# Soccer_Robot_V1_1L.net
KiCad netlist of a schematic drawn in EAGLE
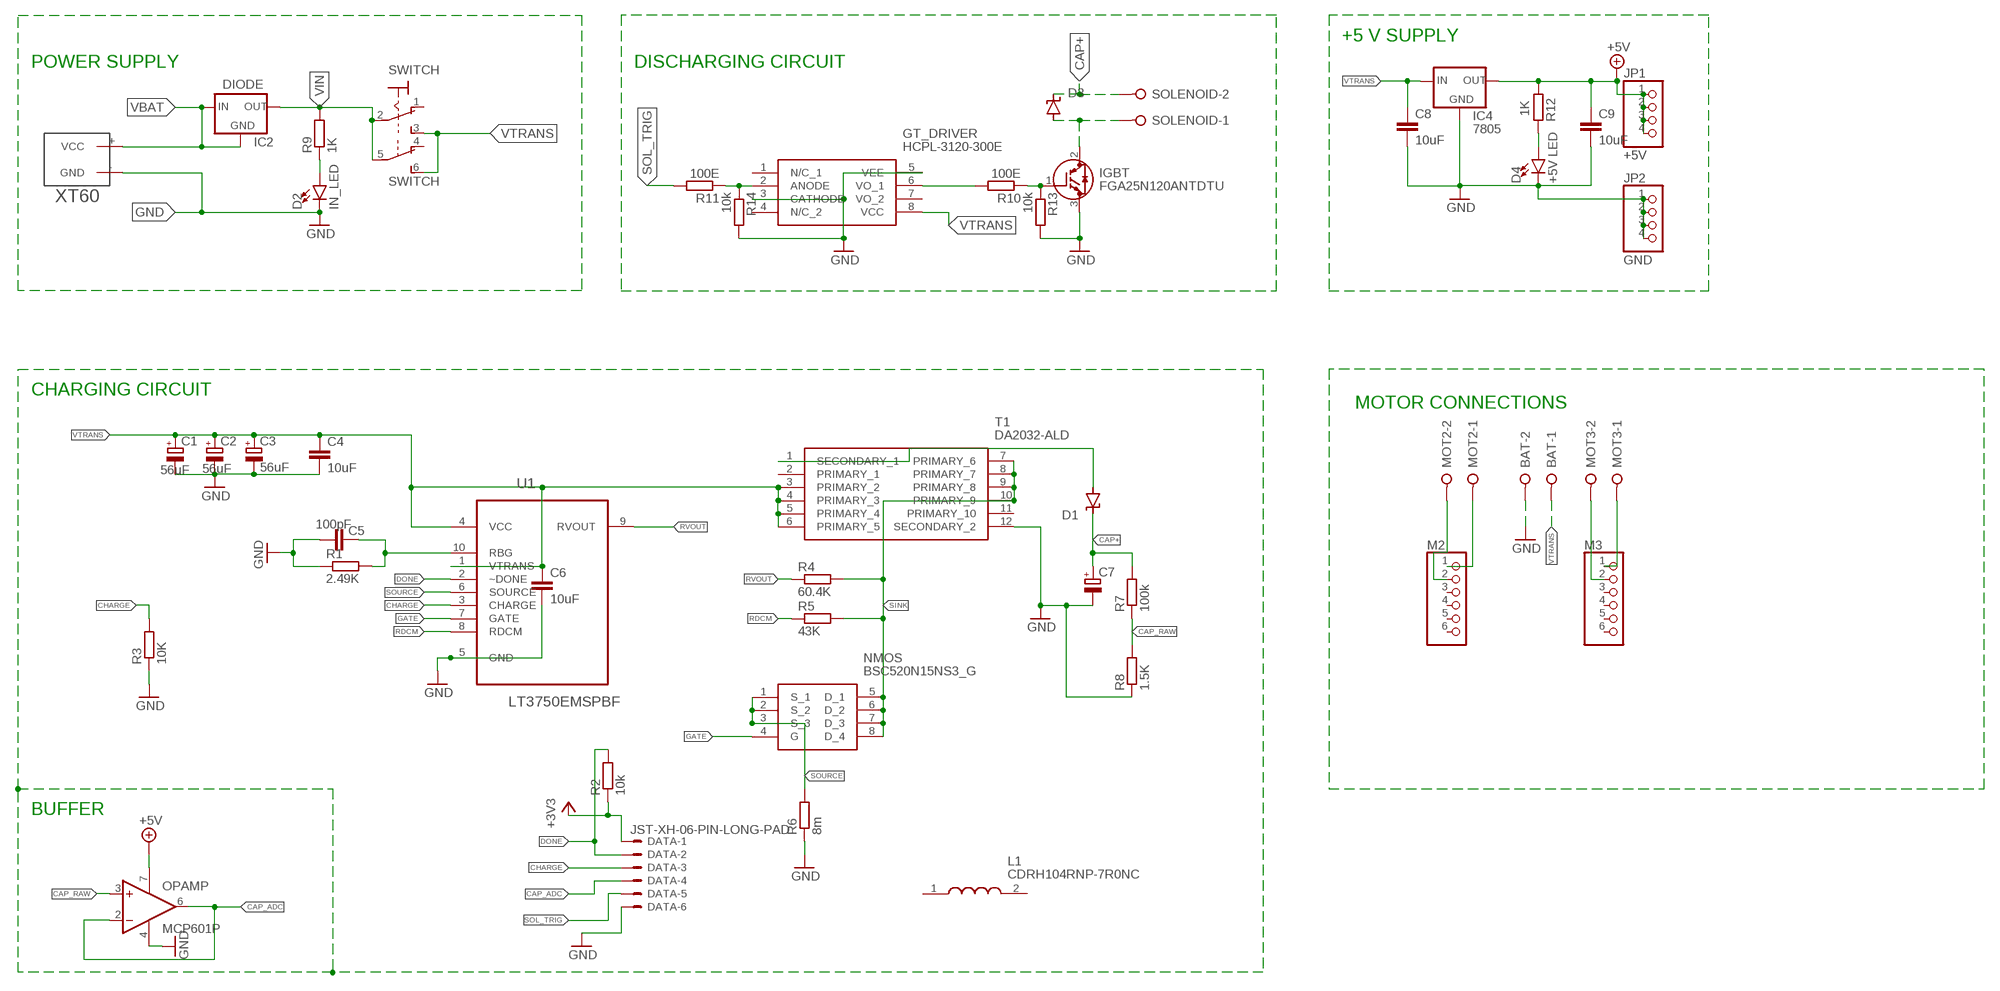
[diagram p0: schematic, sheet 1]

(export (version "E")
  (design (tool "Eeschema 10.0.6"))
  (components
    (comp (ref "BAT")
      (value "W237-02P")
      (footprint "eagle-import:W237-132")
      (libsource (lib "eagle-import") (part "W237-02P"))
    )
    (comp (ref "C1")
      (value "56uF")
      (footprint "eagle-import:E2,5-5")
      (libsource (lib "eagle-import") (part "CPOL-EUE2.5-5"))
    )
    (comp (ref "C2")
      (value "56uF")
      (footprint "eagle-import:E2,5-5")
      (libsource (lib "eagle-import") (part "CPOL-EUE2.5-5"))
    )
    (comp (ref "C3")
      (value "56uF")
      (footprint "eagle-import:E2,5-5")
      (libsource (lib "eagle-import") (part "CPOL-EUE2.5-5"))
    )
    (comp (ref "C4")
      (value "10uF")
      (footprint "eagle-import:C1206")
      (libsource (lib "eagle-import") (part "C-EUC1206"))
    )
    (comp (ref "C5")
      (value "100pF")
      (footprint "eagle-import:C1206")
      (libsource (lib "eagle-import") (part "C-EUC1206"))
    )
    (comp (ref "C6")
      (value "10uF")
      (footprint "eagle-import:C1206")
      (libsource (lib "eagle-import") (part "C-EUC1206"))
    )
    (comp (ref "C7")
      (value "CPOL-EUE10-30")
      (footprint "eagle-import:EB30D")
      (libsource (lib "eagle-import") (part "CPOL-EUE10-30"))
    )
    (comp (ref "C8")
      (value "10uF")
      (footprint "eagle-import:C1206")
      (libsource (lib "eagle-import") (part "C-EUC1206"))
    )
    (comp (ref "C9")
      (value "10uF")
      (footprint "eagle-import:C1206")
      (libsource (lib "eagle-import") (part "C-EUC1206"))
    )
    (comp (ref "D1")
      (value "SUPPRESSOR-SMBG")
      (footprint "eagle-import:SMBG")
      (libsource (lib "eagle-import") (part "SUPPRESSOR-SMBG"))
    )
    (comp (ref "D2")
      (value "IN_LED")
      (footprint "eagle-import:LED_5MM")
      (libsource (lib "eagle-import") (part "LED5MM"))
    )
    (comp (ref "D3")
      (value "SUPPRESSOR-SMBG")
      (footprint "eagle-import:SMBG")
      (libsource (lib "eagle-import") (part "SUPPRESSOR-SMBG"))
    )
    (comp (ref "D4")
      (value "+5V LED")
      (footprint "eagle-import:LED_5MM")
      (libsource (lib "eagle-import") (part "LED5MM"))
    )
    (comp (ref "DATA")
      (value "JST-XH-06-PIN-LONG-PAD")
      (footprint "eagle-import:JST-XH-06-PACKAGE-LONG-PAD")
      (libsource (lib "eagle-import") (part "JST-XH-06-PIN-LONG-PAD"))
    )
    (comp (ref "GT_DRIVER")
      (value "HCPL-3120-300E")
      (footprint "eagle-import:HCPL-3120-GULL-WING")
      (fields (field (name "MOUSER_PART_NUMBER") "630-HCPL-3120-300E"))
      (libsource (lib "eagle-import") (part "HCPL-3120-300E"))
    )
    (comp (ref "IC2")
      (value "DIODE")
      (footprint "eagle-import:TO252")
      (libsource (lib "eagle-import") (part "LM1117TO252"))
    )
    (comp (ref "IC4")
      (value "7805")
      (footprint "eagle-import:78XXS")
      (libsource (lib "eagle-import") (part "78XXS"))
    )
    (comp (ref "IGBT")
      (value "FGA25N120ANTDTU")
      (footprint "eagle-import:TO545P500X1560X2420-3P")
      (fields (field (name "MOUSER_PART_NUMBER") "512-FGA25N120ANTDTU"))
      (libsource (lib "eagle-import") (part "FGA25N120ANTDTU"))
    )
    (comp (ref "JP1")
      (value "+5V")
      (footprint "eagle-import:1X04")
      (libsource (lib "eagle-import") (part "PINHD-1X4"))
    )
    (comp (ref "JP2")
      (value "GND")
      (footprint "eagle-import:1X04")
      (libsource (lib "eagle-import") (part "PINHD-1X4"))
    )
    (comp (ref "L1")
      (value "CDRH104RNP-7R0NC")
      (footprint "eagle-import:CDRH104RNP7R0NC")
      (fields (field (name "MOUSER_PART_NUMBER") "851-CDRH104RNP-7R0NC"))
      (libsource (lib "eagle-import") (part "CDRH104RNP-7R0NC"))
    )
    (comp (ref "M2")
      (value "PINHD-1X6")
      (footprint "eagle-import:1X06")
      (libsource (lib "eagle-import") (part "PINHD-1X6"))
    )
    (comp (ref "M3")
      (value "PINHD-1X6")
      (footprint "eagle-import:1X06")
      (libsource (lib "eagle-import") (part "PINHD-1X6"))
    )
    (comp (ref "MOT2")
      (value "W237-02P")
      (footprint "eagle-import:W237-132")
      (libsource (lib "eagle-import") (part "W237-02P"))
    )
    (comp (ref "MOT3")
      (value "W237-02P")
      (footprint "eagle-import:W237-132")
      (libsource (lib "eagle-import") (part "W237-02P"))
    )
    (comp (ref "NMOS")
      (value "BSC520N15NS3_G")
      (footprint "eagle-import:PG-TDSON-8")
      (fields
        (field (name "MANUFACTURER_PART_NUMBER") "BSC520N15NS3 G")
        (field (name "MOUSER_PART_NUMBER") "726-BSC520N15NS3GXT")
      )
      (libsource (lib "eagle-import") (part "BSC520N15NS3_G"))
    )
    (comp (ref "OPAMP")
      (value "MCP601P")
      (footprint "eagle-import:DIL08")
      (libsource (lib "eagle-import") (part "MCP601P"))
    )
    (comp (ref "R1")
      (value "2.49K")
      (footprint "eagle-import:M1206")
      (libsource (lib "eagle-import") (part "R-EU_M1206"))
    )
    (comp (ref "R2")
      (value "10k")
      (footprint "eagle-import:M1206")
      (libsource (lib "eagle-import") (part "R-EU_M1206"))
    )
    (comp (ref "R3")
      (value "10K")
      (footprint "eagle-import:M1206")
      (libsource (lib "eagle-import") (part "R-EU_M1206"))
    )
    (comp (ref "R4")
      (value "60.4K")
      (footprint "eagle-import:M1206")
      (libsource (lib "eagle-import") (part "R-EU_M1206"))
    )
    (comp (ref "R5")
      (value "43K")
      (footprint "eagle-import:M1206")
      (libsource (lib "eagle-import") (part "R-EU_M1206"))
    )
    (comp (ref "R6")
      (value "8m")
      (footprint "eagle-import:M1206")
      (libsource (lib "eagle-import") (part "R-EU_M1206"))
    )
    (comp (ref "R7")
      (value "100k")
      (footprint "eagle-import:0207_10")
      (libsource (lib "eagle-import") (part "R-EU_0207/10"))
    )
    (comp (ref "R8")
      (value "1.5K")
      (footprint "eagle-import:0207_10")
      (libsource (lib "eagle-import") (part "R-EU_0207/10"))
    )
    (comp (ref "R9")
      (value "1K")
      (footprint "eagle-import:M1206")
      (libsource (lib "eagle-import") (part "R-EU_M1206"))
    )
    (comp (ref "R10")
      (value "100E")
      (footprint "eagle-import:M1206")
      (libsource (lib "eagle-import") (part "R-EU_M1206"))
    )
    (comp (ref "R11")
      (value "100E")
      (footprint "eagle-import:M1206")
      (libsource (lib "eagle-import") (part "R-EU_M1206"))
    )
    (comp (ref "R12")
      (value "1K")
      (footprint "eagle-import:M1206")
      (libsource (lib "eagle-import") (part "R-EU_M1206"))
    )
    (comp (ref "R13")
      (value "10k")
      (footprint "eagle-import:M1206")
      (libsource (lib "eagle-import") (part "R-EU_M1206"))
    )
    (comp (ref "R14")
      (value "10k")
      (footprint "eagle-import:M1206")
      (libsource (lib "eagle-import") (part "R-EU_M1206"))
    )
    (comp (ref "SOLENOID")
      (value "W237-02P")
      (footprint "eagle-import:W237-132")
      (libsource (lib "eagle-import") (part "W237-02P"))
    )
    (comp (ref "SWITCH")
      (value "320-938")
      (footprint "eagle-import:320-938")
      (libsource (lib "eagle-import") (part "320-938"))
    )
    (comp (ref "T1")
      (value "DA2032-ALD")
      (footprint "eagle-import:SOP250P2197X889-12N")
      (fields (field (name "MOUSER_PART_NUMBER") "994-DA2032-ALD"))
      (libsource (lib "eagle-import") (part "DA2032-ALD"))
    )
    (comp (ref "U$1")
      (value "XT60")
      (footprint "eagle-import:XT60")
      (libsource (lib "eagle-import") (part "XT60"))
    )
    (comp (ref "U1")
      (value "LT3750EMSPBF")
      (footprint "eagle-import:SOP50P490X110-10N")
      (fields (field (name "MPN") "LT3750EMS#PBF"))
      (libsource (lib "eagle-import") (part "LT3750EMSPBF"))
    )
  )
  (nets
    (net (code "1") (name "+3V3") (class "Default")
      (node (ref "DATA") (pin "1") (pinfunction "S_1") (pintype "passive"))
      (node (ref "R2") (pin "1") (pinfunction "1_1") (pintype "passive"))
    )
    (net (code "2") (name "+5V") (class "Default")
      (node (ref "C9") (pin "1") (pinfunction "1_1") (pintype "passive"))
      (node (ref "IC4") (pin "OUT") (pinfunction "OUT_OUT") (pintype "passive"))
      (node (ref "JP1") (pin "1") (pinfunction "1_1") (pintype "passive"))
      (node (ref "JP1") (pin "2") (pinfunction "2_2") (pintype "passive"))
      (node (ref "JP1") (pin "3") (pinfunction "3_3") (pintype "passive"))
      (node (ref "JP1") (pin "4") (pinfunction "4_4") (pintype "passive"))
      (node (ref "OPAMP") (pin "7") (pinfunction "V+_7") (pintype "power_in"))
      (node (ref "R12") (pin "1") (pinfunction "1_1") (pintype "passive"))
    )
    (net (code "3") (name "CAP+") (class "Default")
      (node (ref "C7") (pin "+") (pinfunction "+_+") (pintype "passive"))
      (node (ref "D1") (pin "C") (pinfunction "C_C") (pintype "passive"))
      (node (ref "D3") (pin "C") (pinfunction "C_C") (pintype "passive"))
      (node (ref "R7") (pin "2") (pinfunction "2_2") (pintype "passive"))
      (node (ref "SOLENOID") (pin "2") (pinfunction "KL_2") (pintype "passive"))
    )
    (net (code "4") (name "CAP_ADC") (class "Default")
      (node (ref "DATA") (pin "4") (pinfunction "S_4") (pintype "passive"))
      (node (ref "OPAMP") (pin "2") (pinfunction "-IN_2") (pintype "input"))
      (node (ref "OPAMP") (pin "6") (pinfunction "OUT_6") (pintype "output"))
    )
    (net (code "5") (name "CAP_RAW") (class "Default")
      (node (ref "OPAMP") (pin "3") (pinfunction "+IN_3") (pintype "input"))
      (node (ref "R7") (pin "1") (pinfunction "1_1") (pintype "passive"))
      (node (ref "R8") (pin "2") (pinfunction "2_2") (pintype "passive"))
    )
    (net (code "6") (name "CHARGE") (class "Default")
      (node (ref "DATA") (pin "3") (pinfunction "S_3") (pintype "passive"))
      (node (ref "R3") (pin "2") (pinfunction "2_2") (pintype "passive"))
      (node (ref "U1") (pin "3") (pinfunction "CHARGE_3") (pintype "input"))
    )
    (net (code "7") (name "DONE") (class "Default")
      (node (ref "DATA") (pin "2") (pinfunction "S_2") (pintype "passive"))
      (node (ref "R2") (pin "2") (pinfunction "2_2") (pintype "passive"))
      (node (ref "U1") (pin "2") (pinfunction "~{DONE}_2") (pintype "input"))
    )
    (net (code "8") (name "GATE") (class "Default")
      (node (ref "NMOS") (pin "4") (pinfunction "G_4") (pintype "bidirectional"))
      (node (ref "U1") (pin "7") (pinfunction "GATE_7") (pintype "input"))
    )
    (net (code "9") (name "GND") (class "Default")
      (node (ref "BAT") (pin "2") (pinfunction "KL_2") (pintype "passive"))
      (node (ref "C1") (pin "-") (pinfunction "-_-") (pintype "passive"))
      (node (ref "C2") (pin "-") (pinfunction "-_-") (pintype "passive"))
      (node (ref "C3") (pin "-") (pinfunction "-_-") (pintype "passive"))
      (node (ref "C4") (pin "2") (pinfunction "2_2") (pintype "passive"))
      (node (ref "C5") (pin "2") (pinfunction "2_2") (pintype "passive"))
      (node (ref "C6") (pin "2") (pinfunction "2_2") (pintype "passive"))
      (node (ref "C7") (pin "-") (pinfunction "-_-") (pintype "passive"))
      (node (ref "C8") (pin "2") (pinfunction "2_2") (pintype "passive"))
      (node (ref "C9") (pin "2") (pinfunction "2_2") (pintype "passive"))
      (node (ref "D2") (pin "K") (pinfunction "C_K") (pintype "passive"))
      (node (ref "D4") (pin "K") (pinfunction "C_K") (pintype "passive"))
      (node (ref "DATA") (pin "6") (pinfunction "S_6") (pintype "passive"))
      (node (ref "GT_DRIVER") (pin "3") (pinfunction "CATHODE_3") (pintype "bidirectional"))
      (node (ref "GT_DRIVER") (pin "5") (pinfunction "VEE_5") (pintype "bidirectional"))
      (node (ref "IC4") (pin "GND") (pinfunction "GND_GND") (pintype "input"))
      (node (ref "IGBT") (pin "3") (pinfunction "E_3") (pintype "bidirectional"))
      (node (ref "JP2") (pin "1") (pinfunction "1_1") (pintype "passive"))
      (node (ref "JP2") (pin "2") (pinfunction "2_2") (pintype "passive"))
      (node (ref "JP2") (pin "3") (pinfunction "3_3") (pintype "passive"))
      (node (ref "JP2") (pin "4") (pinfunction "4_4") (pintype "passive"))
      (node (ref "OPAMP") (pin "4") (pinfunction "V-_4") (pintype "power_in"))
      (node (ref "R1") (pin "1") (pinfunction "1_1") (pintype "passive"))
      (node (ref "R13") (pin "2") (pinfunction "2_2") (pintype "passive"))
      (node (ref "R14") (pin "2") (pinfunction "2_2") (pintype "passive"))
      (node (ref "R3") (pin "1") (pinfunction "1_1") (pintype "passive"))
      (node (ref "R6") (pin "1") (pinfunction "1_1") (pintype "passive"))
      (node (ref "R8") (pin "1") (pinfunction "1_1") (pintype "passive"))
      (node (ref "T1") (pin "12") (pinfunction "SECONDARY_2_12") (pintype "bidirectional"))
      (node (ref "U$1") (pin "-") (pinfunction "GND_-") (pintype "bidirectional"))
      (node (ref "U1") (pin "5") (pinfunction "GND_5") (pintype "passive"))
    )
    (net (code "10") (name "Net-(D2-PadA)") (class "Default")
      (node (ref "D2") (pin "A") (pinfunction "A_A") (pintype "passive"))
      (node (ref "R9") (pin "1") (pinfunction "1_1") (pintype "passive"))
    )
    (net (code "11") (name "Net-(D4-PadA)") (class "Default")
      (node (ref "D4") (pin "A") (pinfunction "A_A") (pintype "passive"))
      (node (ref "R12") (pin "2") (pinfunction "2_2") (pintype "passive"))
    )
    (net (code "12") (name "Net-(GT_DRIVER-ANODE)") (class "Default")
      (node (ref "GT_DRIVER") (pin "2") (pinfunction "ANODE_2") (pintype "bidirectional"))
      (node (ref "R11") (pin "1") (pinfunction "1_1") (pintype "passive"))
      (node (ref "R14") (pin "1") (pinfunction "1_1") (pintype "passive"))
    )
    (net (code "13") (name "Net-(GT_DRIVER-VO_1)") (class "Default")
      (node (ref "GT_DRIVER") (pin "6") (pinfunction "VO_1_6") (pintype "bidirectional"))
      (node (ref "R10") (pin "2") (pinfunction "2_2") (pintype "passive"))
    )
    (net (code "14") (name "Net-(IGBT-C)") (class "Default")
      (node (ref "D3") (pin "A") (pinfunction "A_A") (pintype "passive"))
      (node (ref "IGBT") (pin "2") (pinfunction "C_2") (pintype "bidirectional"))
      (node (ref "SOLENOID") (pin "1") (pinfunction "KL_1") (pintype "passive"))
    )
    (net (code "15") (name "Net-(IGBT-G)") (class "Default")
      (node (ref "IGBT") (pin "1") (pinfunction "G_1") (pintype "bidirectional"))
      (node (ref "R10") (pin "1") (pinfunction "1_1") (pintype "passive"))
      (node (ref "R13") (pin "1") (pinfunction "1_1") (pintype "passive"))
    )
    (net (code "16") (name "Net-(MOT2A-KL)") (class "Default")
      (node (ref "M2") (pin "1") (pinfunction "1_1") (pintype "passive"))
      (node (ref "MOT2") (pin "1") (pinfunction "KL_1") (pintype "passive"))
    )
    (net (code "17") (name "Net-(MOT2B-KL)") (class "Default")
      (node (ref "M2") (pin "2") (pinfunction "2_2") (pintype "passive"))
      (node (ref "MOT2") (pin "2") (pinfunction "KL_2") (pintype "passive"))
    )
    (net (code "18") (name "Net-(MOT3A-KL)") (class "Default")
      (node (ref "M3") (pin "1") (pinfunction "1_1") (pintype "passive"))
      (node (ref "MOT3") (pin "1") (pinfunction "KL_1") (pintype "passive"))
    )
    (net (code "19") (name "Net-(MOT3B-KL)") (class "Default")
      (node (ref "M3") (pin "2") (pinfunction "2_2") (pintype "passive"))
      (node (ref "MOT3") (pin "2") (pinfunction "KL_2") (pintype "passive"))
    )
    (net (code "20") (name "Net-(T1-SECONDARY_1)") (class "Default")
      (node (ref "D1") (pin "A") (pinfunction "A_A") (pintype "passive"))
      (node (ref "T1") (pin "1") (pinfunction "SECONDARY_1_1") (pintype "bidirectional"))
    )
    (net (code "21") (name "Net-(U1-RBG)") (class "Default")
      (node (ref "C5") (pin "1") (pinfunction "1_1") (pintype "passive"))
      (node (ref "R1") (pin "2") (pinfunction "2_2") (pintype "passive"))
      (node (ref "U1") (pin "10") (pinfunction "RBG_10") (pintype "input"))
    )
    (net (code "22") (name "RDCM") (class "Default")
      (node (ref "R5") (pin "1") (pinfunction "1_1") (pintype "passive"))
      (node (ref "U1") (pin "8") (pinfunction "RDCM_8") (pintype "input"))
    )
    (net (code "23") (name "RVOUT") (class "Default")
      (node (ref "R4") (pin "1") (pinfunction "1_1") (pintype "passive"))
      (node (ref "U1") (pin "9") (pinfunction "RVOUT_9") (pintype "output"))
    )
    (net (code "24") (name "SINK") (class "Default")
      (node (ref "NMOS") (pin "5") (pinfunction "D_1_5") (pintype "bidirectional"))
      (node (ref "NMOS") (pin "6") (pinfunction "D_2_6") (pintype "bidirectional"))
      (node (ref "NMOS") (pin "7") (pinfunction "D_3_7") (pintype "bidirectional"))
      (node (ref "NMOS") (pin "8") (pinfunction "D_4_8") (pintype "bidirectional"))
      (node (ref "R4") (pin "2") (pinfunction "2_2") (pintype "passive"))
      (node (ref "R5") (pin "2") (pinfunction "2_2") (pintype "passive"))
      (node (ref "T1") (pin "10") (pinfunction "PRIMARY_9_10") (pintype "bidirectional"))
      (node (ref "T1") (pin "7") (pinfunction "PRIMARY_6_7") (pintype "bidirectional"))
      (node (ref "T1") (pin "8") (pinfunction "PRIMARY_7_8") (pintype "bidirectional"))
      (node (ref "T1") (pin "9") (pinfunction "PRIMARY_8_9") (pintype "bidirectional"))
    )
    (net (code "25") (name "SOL_TRIG") (class "Default")
      (node (ref "DATA") (pin "5") (pinfunction "S_5") (pintype "passive"))
      (node (ref "R11") (pin "2") (pinfunction "2_2") (pintype "passive"))
    )
    (net (code "26") (name "SOURCE") (class "Default")
      (node (ref "NMOS") (pin "1") (pinfunction "S_1_1") (pintype "bidirectional"))
      (node (ref "NMOS") (pin "2") (pinfunction "S_2_2") (pintype "bidirectional"))
      (node (ref "NMOS") (pin "3") (pinfunction "S_3_3") (pintype "bidirectional"))
      (node (ref "R6") (pin "2") (pinfunction "2_2") (pintype "passive"))
      (node (ref "U1") (pin "6") (pinfunction "SOURCE_6") (pintype "input"))
    )
    (net (code "27") (name "VBAT") (class "Default")
      (node (ref "IC2") (pin "1") (pinfunction "GND_1") (pintype "input"))
      (node (ref "IC2") (pin "2") (pinfunction "IN_2") (pintype "input"))
      (node (ref "U$1") (pin "+") (pinfunction "VCC_+") (pintype "bidirectional"))
    )
    (net (code "28") (name "VIN") (class "Default")
      (node (ref "IC2") (pin "3") (pinfunction "OUT_3") (pintype "passive"))
      (node (ref "R9") (pin "2") (pinfunction "2_2") (pintype "passive"))
      (node (ref "SWITCH") (pin "2") (pinfunction "P_2") (pintype "passive"))
      (node (ref "SWITCH") (pin "5") (pinfunction "P_5") (pintype "passive"))
    )
    (net (code "29") (name "VTRANS") (class "Default")
      (node (ref "BAT") (pin "1") (pinfunction "KL_1") (pintype "passive"))
      (node (ref "C1") (pin "+") (pinfunction "+_+") (pintype "passive"))
      (node (ref "C2") (pin "+") (pinfunction "+_+") (pintype "passive"))
      (node (ref "C3") (pin "+") (pinfunction "+_+") (pintype "passive"))
      (node (ref "C4") (pin "1") (pinfunction "1_1") (pintype "passive"))
      (node (ref "C6") (pin "1") (pinfunction "1_1") (pintype "passive"))
      (node (ref "C8") (pin "1") (pinfunction "1_1") (pintype "passive"))
      (node (ref "GT_DRIVER") (pin "8") (pinfunction "VCC_8") (pintype "bidirectional"))
      (node (ref "IC4") (pin "IN") (pinfunction "IN_IN") (pintype "input"))
      (node (ref "SWITCH") (pin "3") (pinfunction "S_3") (pintype "passive"))
      (node (ref "SWITCH") (pin "6") (pinfunction "S_6") (pintype "passive"))
      (node (ref "T1") (pin "3") (pinfunction "PRIMARY_2_3") (pintype "bidirectional"))
      (node (ref "T1") (pin "4") (pinfunction "PRIMARY_3_4") (pintype "bidirectional"))
      (node (ref "T1") (pin "5") (pinfunction "PRIMARY_4_5") (pintype "bidirectional"))
      (node (ref "T1") (pin "6") (pinfunction "PRIMARY_5_6") (pintype "bidirectional"))
      (node (ref "U1") (pin "1") (pinfunction "VTRANS_1") (pintype "power_in"))
      (node (ref "U1") (pin "4") (pinfunction "VCC_4") (pintype "power_in"))
    )
    (net (code "30") (name "unconnected-(GT_DRIVER-N{slash}C_1-Pad1)") (class "Default")
      (node (ref "GT_DRIVER") (pin "1") (pinfunction "N/C_1_1") (pintype "bidirectional"))
    )
    (net (code "31") (name "unconnected-(GT_DRIVER-N{slash}C_2-Pad4)") (class "Default")
      (node (ref "GT_DRIVER") (pin "4") (pinfunction "N/C_2_4") (pintype "bidirectional"))
    )
    (net (code "32") (name "unconnected-(GT_DRIVER-VO_2-Pad7)") (class "Default")
      (node (ref "GT_DRIVER") (pin "7") (pinfunction "VO_2_7") (pintype "bidirectional"))
    )
    (net (code "33") (name "unconnected-(L1-Pad1)") (class "Default")
      (node (ref "L1") (pin "1") (pinfunction "1_1") (pintype "bidirectional"))
    )
    (net (code "34") (name "unconnected-(L1-Pad2)") (class "Default")
      (node (ref "L1") (pin "2") (pinfunction "2_2") (pintype "bidirectional"))
    )
    (net (code "35") (name "unconnected-(M2-Pad3)") (class "Default")
      (node (ref "M2") (pin "3") (pinfunction "3_3") (pintype "passive"))
    )
    (net (code "36") (name "unconnected-(M2-Pad4)") (class "Default")
      (node (ref "M2") (pin "4") (pinfunction "4_4") (pintype "passive"))
    )
    (net (code "37") (name "unconnected-(M2-Pad5)") (class "Default")
      (node (ref "M2") (pin "5") (pinfunction "5_5") (pintype "passive"))
    )
    (net (code "38") (name "unconnected-(M2-Pad6)") (class "Default")
      (node (ref "M2") (pin "6") (pinfunction "6_6") (pintype "passive"))
    )
    (net (code "39") (name "unconnected-(M3-Pad3)") (class "Default")
      (node (ref "M3") (pin "3") (pinfunction "3_3") (pintype "passive"))
    )
    (net (code "40") (name "unconnected-(M3-Pad4)") (class "Default")
      (node (ref "M3") (pin "4") (pinfunction "4_4") (pintype "passive"))
    )
    (net (code "41") (name "unconnected-(M3-Pad5)") (class "Default")
      (node (ref "M3") (pin "5") (pinfunction "5_5") (pintype "passive"))
    )
    (net (code "42") (name "unconnected-(M3-Pad6)") (class "Default")
      (node (ref "M3") (pin "6") (pinfunction "6_6") (pintype "passive"))
    )
    (net (code "43") (name "unconnected-(SWITCHA-O-Pad1)") (class "Default")
      (node (ref "SWITCH") (pin "1") (pinfunction "O_1") (pintype "passive"))
    )
    (net (code "44") (name "unconnected-(SWITCHB-O-Pad4)") (class "Default")
      (node (ref "SWITCH") (pin "4") (pinfunction "O_4") (pintype "passive"))
    )
    (net (code "45") (name "unconnected-(T1-PRIMARY_1-Pad2)") (class "Default")
      (node (ref "T1") (pin "2") (pinfunction "PRIMARY_1_2") (pintype "bidirectional"))
    )
    (net (code "46") (name "unconnected-(T1-PRIMARY_10-Pad11)") (class "Default")
      (node (ref "T1") (pin "11") (pinfunction "PRIMARY_10_11") (pintype "bidirectional"))
    )
  )
)
